# Power_Supply.net
KiCad netlist of a schematic drawn in Altium Designer
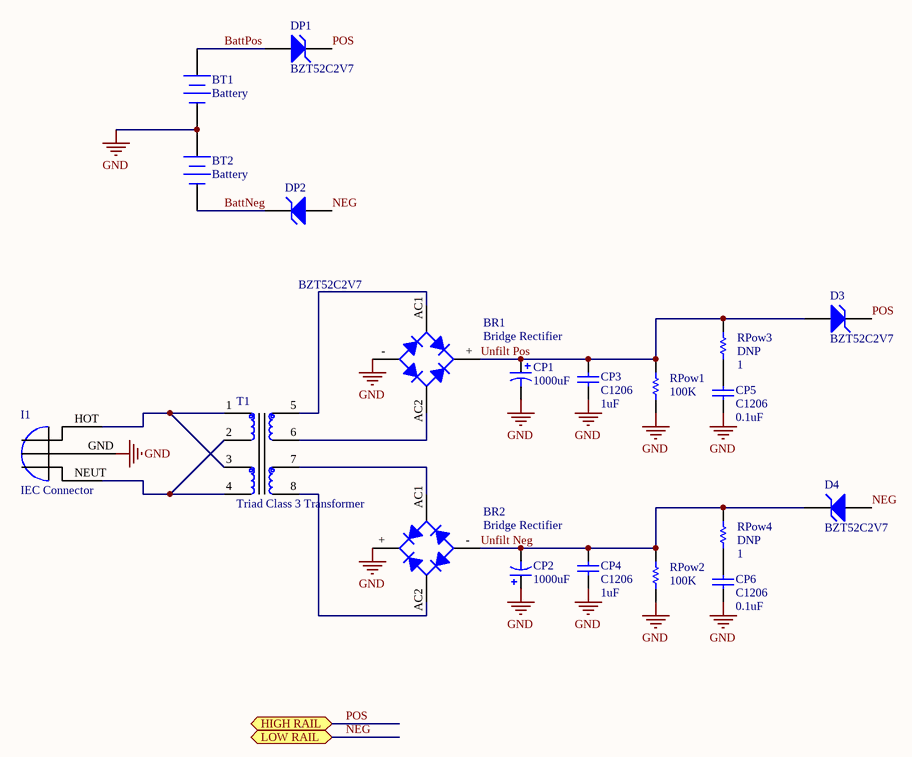
[diagram p0: Power Supply.SchDoc]

(export (version "E")
  (design (tool "Eeschema 10.0.6"))
  (components
    (comp (ref "BR1")
      (value "Bridge Rectifier")
      (footprint "Bridge Rectifier")
      (libsource (lib "Custom Parts") (part "Bridge Rectifier"))
    )
    (comp (ref "BR2")
      (value "Bridge Rectifier")
      (footprint "Bridge Rectifier")
      (libsource (lib "Custom Parts") (part "Bridge Rectifier"))
    )
    (comp (ref "BT1")
      (value "Battery")
      (footprint "BAT-2")
      (description "Multicell Battery")
      (fields (field (name "PUBLISHER") "Altium Limited"))
      (libsource (lib "Miscellaneous Devices") (part "Battery"))
    )
    (comp (ref "BT2")
      (value "Battery")
      (footprint "BAT-2")
      (description "Multicell Battery")
      (fields (field (name "PUBLISHER") "Altium Limited"))
      (libsource (lib "Miscellaneous Devices") (part "Battery"))
    )
    (comp (ref "CP1")
      (value "1000uF")
      (footprint "CAPPR7.5-16X25")
      (description "Aluminum Electrolytic Capacitor, Radial Style with Long Leads: 47uF, 350V")
      (fields (field (name "PUBLISHER") "Altium Limited"))
      (libsource (lib "Vishay Roederstein Electrolytic Radial-Lead Capacitor") (part "EKA00JG247O00"))
    )
    (comp (ref "CP2")
      (value "1000uF")
      (footprint "CAPPR7.5-16X25")
      (description "Aluminum Electrolytic Capacitor, Radial Style with Long Leads: 47uF, 350V")
      (fields (field (name "PUBLISHER") "Altium Limited"))
      (libsource (lib "Vishay Roederstein Electrolytic Radial-Lead Capacitor") (part "EKA00JG247O00"))
    )
    (comp (ref "CP3")
      (value "C1206")
      (footprint "1206")
      (description "Ceramic Chip Capacitor - Standard")
      (fields (field (name "ALTIUM_VALUE") "1uF") (field (name "PUBLISHER") "Altium Limited"))
      (libsource (lib "KEMET Chip Capacitor") (part "C1206"))
    )
    (comp (ref "CP4")
      (value "C1206")
      (footprint "1206")
      (description "Ceramic Chip Capacitor - Standard")
      (fields (field (name "ALTIUM_VALUE") "1uF") (field (name "PUBLISHER") "Altium Limited"))
      (libsource (lib "KEMET Chip Capacitor") (part "C1206"))
    )
    (comp (ref "CP5")
      (value "C1206")
      (footprint "1206")
      (description "Ceramic Chip Capacitor - Standard")
      (fields (field (name "ALTIUM_VALUE") "0.1uF") (field (name "PUBLISHER") "Altium Limited"))
      (libsource (lib "KEMET Chip Capacitor") (part "C1206"))
    )
    (comp (ref "CP6")
      (value "C1206")
      (footprint "1206")
      (description "Ceramic Chip Capacitor - Standard")
      (fields (field (name "ALTIUM_VALUE") "0.1uF") (field (name "PUBLISHER") "Altium Limited"))
      (libsource (lib "KEMET Chip Capacitor") (part "C1206"))
    )
    (comp (ref "D3")
      (value "BZT52C2V7")
      (footprint "SOD-123")
      (description "Surface Mount Zener Diode")
      (fields (field (name "PUBLISHER") "Altium Limited"))
      (libsource (lib "Vishay Lite-On Discrete Diode") (part "BZT52C2V7"))
    )
    (comp (ref "D4")
      (value "BZT52C2V7")
      (footprint "SOD-123")
      (description "Surface Mount Zener Diode")
      (fields (field (name "PUBLISHER") "Altium Limited"))
      (libsource (lib "Vishay Lite-On Discrete Diode") (part "BZT52C2V7"))
    )
    (comp (ref "DP1")
      (value "BZT52C2V7")
      (footprint "SOD-123")
      (description "Surface Mount Zener Diode")
      (fields (field (name "PUBLISHER") "Altium Limited"))
      (libsource (lib "Vishay Lite-On Discrete Diode") (part "BZT52C2V7"))
    )
    (comp (ref "DP2")
      (value "BZT52C2V7")
      (footprint "SOD-123")
      (description "Surface Mount Zener Diode")
      (fields (field (name "PUBLISHER") "Altium Limited"))
      (libsource (lib "Vishay Lite-On Discrete Diode") (part "BZT52C2V7"))
    )
    (comp (ref "I1")
      (value "IEC Connector")
      (footprint "IEC Connector")
      (libsource (lib "Custom Parts") (part "IEC Connector"))
    )
    (comp (ref "RPow1")
      (value "100K")
      (footprint "ERA-0805")
      (fields (field (name "PUBLISHER") "Altium Limited"))
      (libsource (lib "Panasonic Resistor") (part "ERA6Y"))
    )
    (comp (ref "RPow2")
      (value "100K")
      (footprint "ERA-0805")
      (fields (field (name "PUBLISHER") "Altium Limited"))
      (libsource (lib "Panasonic Resistor") (part "ERA6Y"))
    )
    (comp (ref "RPow3")
      (value "DNP")
      (footprint "ERA-0805")
      (fields (field (name "ALTIUM_VALUE") "1") (field (name "PUBLISHER") "Altium Limited"))
      (libsource (lib "Panasonic Resistor") (part "ERA6Y"))
    )
    (comp (ref "RPow4")
      (value "DNP")
      (footprint "ERA-0805")
      (fields (field (name "ALTIUM_VALUE") "1") (field (name "PUBLISHER") "Altium Limited"))
      (libsource (lib "Panasonic Resistor") (part "ERA6Y"))
    )
    (comp (ref "T1")
      (value "Triad Class 3 Transformer")
      (footprint "TRIAD CLASS 3 TRANSFORMER")
      (libsource (lib "Custom Parts") (part "Triad Class 3 Transformer"))
    )
  )
  (nets
    (net (code "1") (name "/BattNeg") (class "Default")
      (node (ref "BT2") (pin "2") (pinfunction "-_2") (pintype "passive"))
      (node (ref "DP2") (pin "2") (pinfunction "K_2") (pintype "passive"))
    )
    (net (code "2") (name "/BattPos") (class "Default")
      (node (ref "BT1") (pin "1") (pinfunction "+_1") (pintype "passive"))
      (node (ref "DP1") (pin "1") (pinfunction "A_1") (pintype "passive"))
    )
    (net (code "3") (name "/NEG") (class "Default")
      (node (ref "D4") (pin "1") (pinfunction "A_1") (pintype "passive"))
      (node (ref "DP2") (pin "1") (pinfunction "A_1") (pintype "passive"))
    )
    (net (code "4") (name "/POS") (class "Default")
      (node (ref "D3") (pin "2") (pinfunction "K_2") (pintype "passive"))
      (node (ref "DP1") (pin "2") (pinfunction "K_2") (pintype "passive"))
    )
    (net (code "5") (name "/Unfilt Neg") (class "Default")
      (node (ref "BR2") (pin "-") (pinfunction "-_-") (pintype "passive"))
      (node (ref "CP2") (pin "2") (pinfunction "2_2") (pintype "passive"))
      (node (ref "CP4") (pin "2") (pinfunction "2_2") (pintype "passive"))
      (node (ref "D4") (pin "2") (pinfunction "K_2") (pintype "passive"))
      (node (ref "RPow2") (pin "2") (pinfunction "2_2") (pintype "passive"))
      (node (ref "RPow4") (pin "2") (pinfunction "2_2") (pintype "passive"))
    )
    (net (code "6") (name "/Unfilt Pos") (class "Default")
      (node (ref "BR1") (pin "+") (pinfunction "+_+") (pintype "passive"))
      (node (ref "CP1") (pin "1") (pinfunction "1_1") (pintype "passive"))
      (node (ref "CP3") (pin "2") (pinfunction "2_2") (pintype "passive"))
      (node (ref "D3") (pin "1") (pinfunction "A_1") (pintype "passive"))
      (node (ref "RPow1") (pin "2") (pinfunction "2_2") (pintype "passive"))
      (node (ref "RPow3") (pin "2") (pinfunction "2_2") (pintype "passive"))
    )
    (net (code "7") (name "GND") (class "Default")
      (node (ref "BR1") (pin "-") (pinfunction "-_-") (pintype "passive"))
      (node (ref "BR2") (pin "+") (pinfunction "+_+") (pintype "passive"))
      (node (ref "BT1") (pin "2") (pinfunction "-_2") (pintype "passive"))
      (node (ref "BT2") (pin "1") (pinfunction "+_1") (pintype "passive"))
      (node (ref "CP1") (pin "2") (pinfunction "2_2") (pintype "passive"))
      (node (ref "CP2") (pin "1") (pinfunction "1_1") (pintype "passive"))
      (node (ref "CP3") (pin "1") (pinfunction "1_1") (pintype "passive"))
      (node (ref "CP4") (pin "1") (pinfunction "1_1") (pintype "passive"))
      (node (ref "CP5") (pin "1") (pinfunction "1_1") (pintype "passive"))
      (node (ref "CP6") (pin "1") (pinfunction "1_1") (pintype "passive"))
      (node (ref "I1") (pin "GND") (pinfunction "GND_GND") (pintype "passive"))
      (node (ref "RPow1") (pin "1") (pinfunction "1_1") (pintype "passive"))
      (node (ref "RPow2") (pin "1") (pinfunction "1_1") (pintype "passive"))
    )
    (net (code "8") (name "Net-(BR1-PadAC1)") (class "Default")
      (node (ref "BR1") (pin "AC1") (pinfunction "AC1_AC1") (pintype "passive"))
      (node (ref "T1") (pin "5") (pinfunction "5_5") (pintype "passive"))
    )
    (net (code "9") (name "Net-(BR1-PadAC2)") (class "Default")
      (node (ref "BR1") (pin "AC2") (pinfunction "AC2_AC2") (pintype "passive"))
      (node (ref "T1") (pin "6") (pinfunction "6_6") (pintype "passive"))
    )
    (net (code "10") (name "Net-(BR2-PadAC1)") (class "Default")
      (node (ref "BR2") (pin "AC1") (pinfunction "AC1_AC1") (pintype "passive"))
      (node (ref "T1") (pin "7") (pinfunction "7_7") (pintype "passive"))
    )
    (net (code "11") (name "Net-(BR2-PadAC2)") (class "Default")
      (node (ref "BR2") (pin "AC2") (pinfunction "AC2_AC2") (pintype "passive"))
      (node (ref "T1") (pin "8") (pinfunction "8_8") (pintype "passive"))
    )
    (net (code "12") (name "Net-(CP5-Pad2)") (class "Default")
      (node (ref "CP5") (pin "2") (pinfunction "2_2") (pintype "passive"))
      (node (ref "RPow3") (pin "1") (pinfunction "1_1") (pintype "passive"))
    )
    (net (code "13") (name "Net-(CP6-Pad2)") (class "Default")
      (node (ref "CP6") (pin "2") (pinfunction "2_2") (pintype "passive"))
      (node (ref "RPow4") (pin "1") (pinfunction "1_1") (pintype "passive"))
    )
    (net (code "14") (name "Net-(I1-PadHOT)") (class "Default")
      (node (ref "I1") (pin "HOT") (pinfunction "HOT_HOT") (pintype "passive"))
      (node (ref "T1") (pin "1") (pinfunction "1_1") (pintype "passive"))
      (node (ref "T1") (pin "3") (pinfunction "3_3") (pintype "passive"))
    )
    (net (code "15") (name "Net-(I1-PadNEUT)") (class "Default")
      (node (ref "I1") (pin "NEUT") (pinfunction "NEUT_NEUT") (pintype "passive"))
      (node (ref "T1") (pin "2") (pinfunction "2_2") (pintype "passive"))
      (node (ref "T1") (pin "4") (pinfunction "4_4") (pintype "passive"))
    )
  )
)
